# 02_ESP32.net
KiCad netlist of a schematic drawn in Altium Designer
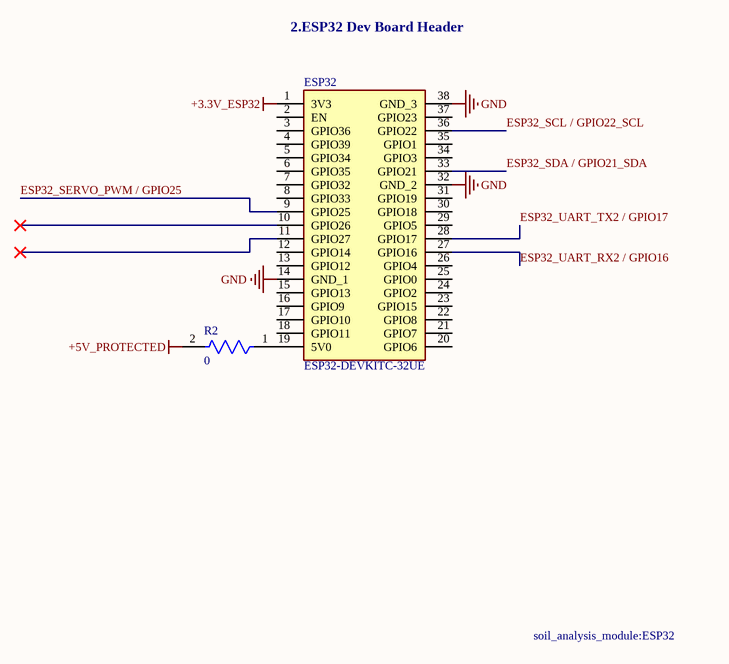
[diagram p0: 02_ESP32.SchDoc]

(export (version "E")
  (design (tool "Eeschema 10.0.6"))
  (components
    (comp (ref "ESP32")
      (value "ESP32-DEVKITC-32UE")
      (footprint "ESP32-DEVKITC-32UE-Footprint-1")
      (libsource (lib "Maksym Pleshyvtsev") (part "ESP32-DEVKITC-32UE-Symbol-1"))
    )
    (comp (ref "R2")
      (value "0")
      (footprint "FP-RC1206-MFG")
      (description "GENERAL PURPOSE CHIP RESISTOR Metal Glaze/thick Film, 0.25W, 0ohm, Surface Mount, 1206")
      (fields (field (name "TOLERANCE") "5%") (field (name "Comment") "RC1206JR-070RL"))
      (libsource (lib "Maksym Pleshyvtsev") (part "1029c3af85768c4190bb7ad29bc67b5"))
    )
  )
  (nets
    (net (code "1") (name "+3.3V_ESP32") (class "Default")
      (node (ref "ESP32") (pin "1") (pinfunction "3V3_1") (pintype "passive"))
    )
    (net (code "2") (name "+5V_PROTECTED") (class "Default")
      (node (ref "R2") (pin "2") (pinfunction "2_2") (pintype "passive"))
    )
    (net (code "3") (name "/ESP32_SCL {slash} GPIO22_SCL") (class "Default")
      (node (ref "ESP32") (pin "36") (pinfunction "GPIO22_36") (pintype "passive"))
    )
    (net (code "4") (name "/ESP32_SDA {slash} GPIO21_SDA") (class "Default")
      (node (ref "ESP32") (pin "33") (pinfunction "GPIO21_33") (pintype "passive"))
    )
    (net (code "5") (name "/ESP32_SERVO_PWM {slash} GPIO25") (class "Default")
      (node (ref "ESP32") (pin "9") (pinfunction "GPIO25_9") (pintype "passive"))
    )
    (net (code "6") (name "/ESP32_UART_RX2 {slash} GPIO16") (class "Default")
      (node (ref "ESP32") (pin "27") (pinfunction "GPIO16_27") (pintype "passive"))
    )
    (net (code "7") (name "/ESP32_UART_TX2 {slash} GPIO17") (class "Default")
      (node (ref "ESP32") (pin "28") (pinfunction "GPIO17_28") (pintype "passive"))
    )
    (net (code "8") (name "GND") (class "Default")
      (node (ref "ESP32") (pin "14") (pinfunction "GND_1_14") (pintype "passive"))
      (node (ref "ESP32") (pin "32") (pinfunction "GND_2_32") (pintype "passive"))
      (node (ref "ESP32") (pin "38") (pinfunction "GND_3_38") (pintype "passive"))
    )
    (net (code "9") (name "Net-(ESP32-5V0)") (class "Default")
      (node (ref "ESP32") (pin "19") (pinfunction "5V0_19") (pintype "passive"))
      (node (ref "R2") (pin "1") (pinfunction "1_1") (pintype "passive"))
    )
    (net (code "10") (name "unconnected-(ESP32-EN-Pad2)") (class "Default")
      (node (ref "ESP32") (pin "2") (pinfunction "EN_2") (pintype "passive"))
    )
    (net (code "11") (name "unconnected-(ESP32-GPIO0-Pad25)") (class "Default")
      (node (ref "ESP32") (pin "25") (pinfunction "GPIO0_25") (pintype "passive"))
    )
    (net (code "12") (name "unconnected-(ESP32-GPIO1-Pad35)") (class "Default")
      (node (ref "ESP32") (pin "35") (pinfunction "GPIO1_35") (pintype "passive"))
    )
    (net (code "13") (name "unconnected-(ESP32-GPIO2-Pad24)") (class "Default")
      (node (ref "ESP32") (pin "24") (pinfunction "GPIO2_24") (pintype "passive"))
    )
    (net (code "14") (name "unconnected-(ESP32-GPIO3-Pad34)") (class "Default")
      (node (ref "ESP32") (pin "34") (pinfunction "GPIO3_34") (pintype "passive"))
    )
    (net (code "15") (name "unconnected-(ESP32-GPIO4-Pad26)") (class "Default")
      (node (ref "ESP32") (pin "26") (pinfunction "GPIO4_26") (pintype "passive"))
    )
    (net (code "16") (name "unconnected-(ESP32-GPIO5-Pad29)") (class "Default")
      (node (ref "ESP32") (pin "29") (pinfunction "GPIO5_29") (pintype "passive"))
    )
    (net (code "17") (name "unconnected-(ESP32-GPIO6-Pad20)") (class "Default")
      (node (ref "ESP32") (pin "20") (pinfunction "GPIO6_20") (pintype "passive"))
    )
    (net (code "18") (name "unconnected-(ESP32-GPIO7-Pad21)") (class "Default")
      (node (ref "ESP32") (pin "21") (pinfunction "GPIO7_21") (pintype "passive"))
    )
    (net (code "19") (name "unconnected-(ESP32-GPIO8-Pad22)") (class "Default")
      (node (ref "ESP32") (pin "22") (pinfunction "GPIO8_22") (pintype "passive"))
    )
    (net (code "20") (name "unconnected-(ESP32-GPIO9-Pad16)") (class "Default")
      (node (ref "ESP32") (pin "16") (pinfunction "GPIO9_16") (pintype "passive"))
    )
    (net (code "21") (name "unconnected-(ESP32-GPIO10-Pad17)") (class "Default")
      (node (ref "ESP32") (pin "17") (pinfunction "GPIO10_17") (pintype "passive"))
    )
    (net (code "22") (name "unconnected-(ESP32-GPIO11-Pad18)") (class "Default")
      (node (ref "ESP32") (pin "18") (pinfunction "GPIO11_18") (pintype "passive"))
    )
    (net (code "23") (name "unconnected-(ESP32-GPIO12-Pad13)") (class "Default")
      (node (ref "ESP32") (pin "13") (pinfunction "GPIO12_13") (pintype "passive"))
    )
    (net (code "24") (name "unconnected-(ESP32-GPIO13-Pad15)") (class "Default")
      (node (ref "ESP32") (pin "15") (pinfunction "GPIO13_15") (pintype "passive"))
    )
    (net (code "25") (name "unconnected-(ESP32-GPIO14-Pad12)") (class "Default")
      (node (ref "ESP32") (pin "12") (pinfunction "GPIO14_12") (pintype "passive"))
    )
    (net (code "26") (name "unconnected-(ESP32-GPIO15-Pad23)") (class "Default")
      (node (ref "ESP32") (pin "23") (pinfunction "GPIO15_23") (pintype "passive"))
    )
    (net (code "27") (name "unconnected-(ESP32-GPIO18-Pad30)") (class "Default")
      (node (ref "ESP32") (pin "30") (pinfunction "GPIO18_30") (pintype "passive"))
    )
    (net (code "28") (name "unconnected-(ESP32-GPIO19-Pad31)") (class "Default")
      (node (ref "ESP32") (pin "31") (pinfunction "GPIO19_31") (pintype "passive"))
    )
    (net (code "29") (name "unconnected-(ESP32-GPIO23-Pad37)") (class "Default")
      (node (ref "ESP32") (pin "37") (pinfunction "GPIO23_37") (pintype "passive"))
    )
    (net (code "30") (name "unconnected-(ESP32-GPIO26-Pad10)") (class "Default")
      (node (ref "ESP32") (pin "10") (pinfunction "GPIO26_10") (pintype "passive+no_connect"))
    )
    (net (code "31") (name "unconnected-(ESP32-GPIO27-Pad11)") (class "Default")
      (node (ref "ESP32") (pin "11") (pinfunction "GPIO27_11") (pintype "passive+no_connect"))
    )
    (net (code "32") (name "unconnected-(ESP32-GPIO32-Pad7)") (class "Default")
      (node (ref "ESP32") (pin "7") (pinfunction "GPIO32_7") (pintype "passive"))
    )
    (net (code "33") (name "unconnected-(ESP32-GPIO33-Pad8)") (class "Default")
      (node (ref "ESP32") (pin "8") (pinfunction "GPIO33_8") (pintype "passive"))
    )
    (net (code "34") (name "unconnected-(ESP32-GPIO34-Pad5)") (class "Default")
      (node (ref "ESP32") (pin "5") (pinfunction "GPIO34_5") (pintype "passive"))
    )
    (net (code "35") (name "unconnected-(ESP32-GPIO35-Pad6)") (class "Default")
      (node (ref "ESP32") (pin "6") (pinfunction "GPIO35_6") (pintype "passive"))
    )
    (net (code "36") (name "unconnected-(ESP32-GPIO36-Pad3)") (class "Default")
      (node (ref "ESP32") (pin "3") (pinfunction "GPIO36_3") (pintype "passive"))
    )
    (net (code "37") (name "unconnected-(ESP32-GPIO39-Pad4)") (class "Default")
      (node (ref "ESP32") (pin "4") (pinfunction "GPIO39_4") (pintype "passive"))
    )
  )
)
